# touch-24.net
KiCad netlist of a schematic drawn in Altium Designer
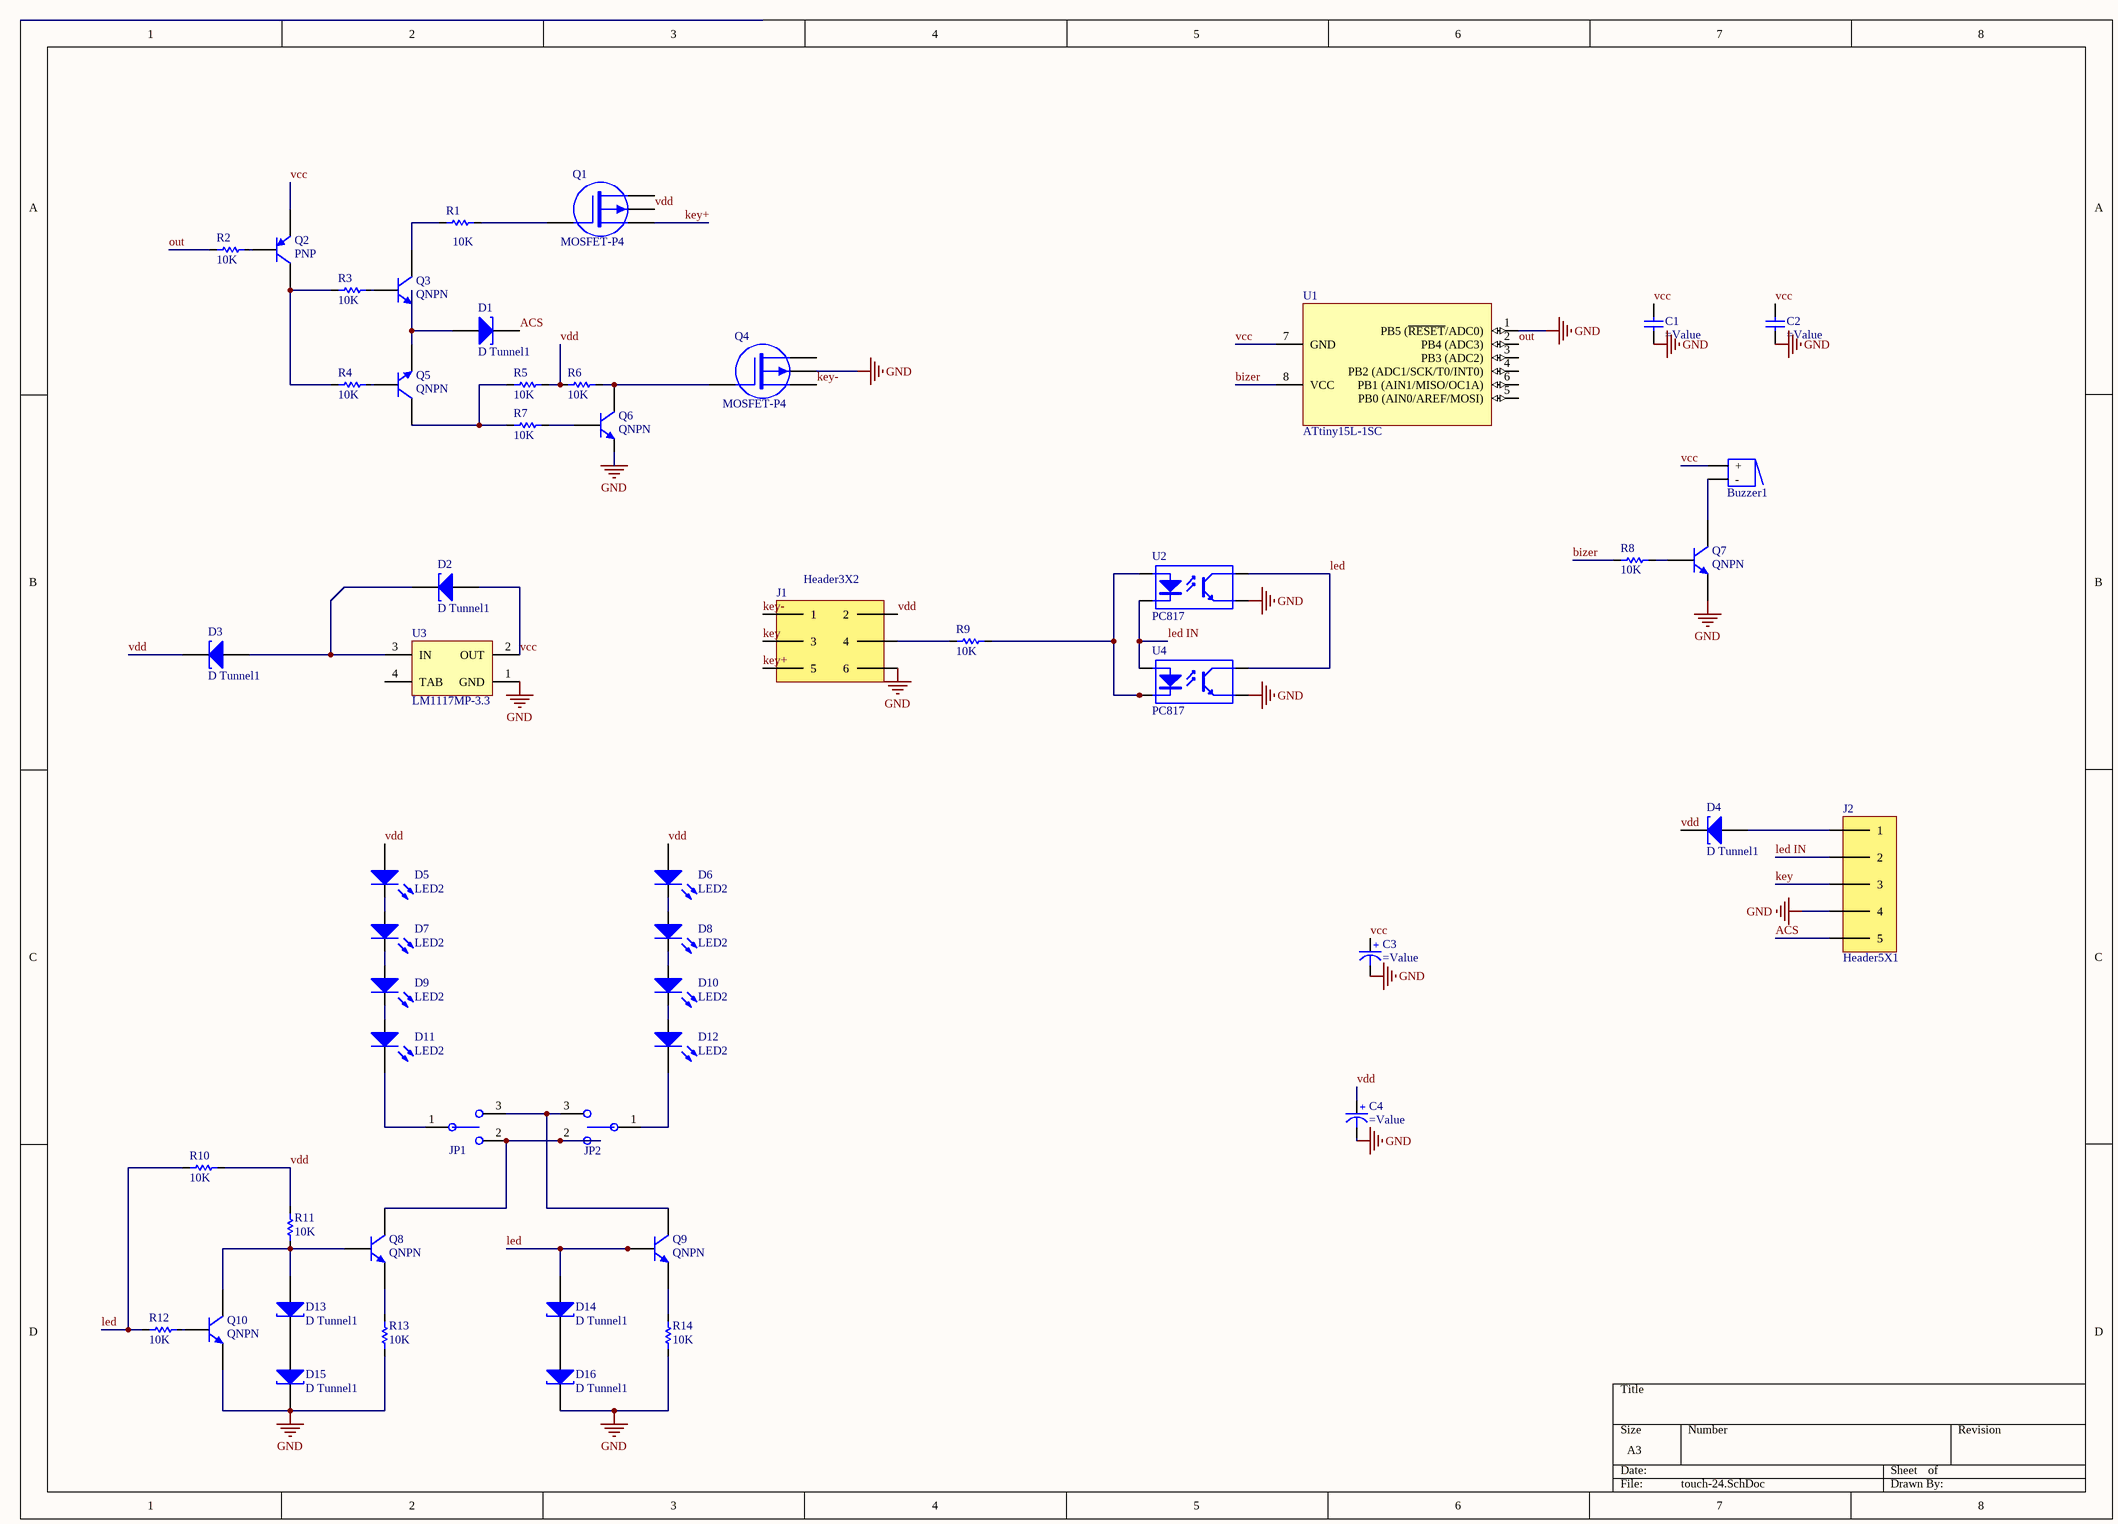
[diagram p0: touch-24.SchDoc]

(export (version "E")
  (design (tool "Eeschema 10.0.6"))
  (components
    (comp (ref "Buzzer1")
      (value "Buzzer")
      (footprint "BUZZER")
      (fields (field (name "DESIGNER") "Seyed Mohsen Ghasemain"))
      (libsource (lib "PicPars.com_usefully_Library") (part "Buzzer"))
    )
    (comp (ref "C1")
      (value "~")
      (footprint "CAP 1206")
      (description "Capacitor")
      (libsource (lib "AltiumLib1") (part "Capacitor"))
    )
    (comp (ref "C2")
      (value "~")
      (footprint "CAP 1206")
      (description "Capacitor")
      (libsource (lib "AltiumLib1") (part "Capacitor"))
    )
    (comp (ref "C3")
      (value "~")
      (footprint "ELEC-CAP-RAD10-20")
      (description "Electrolytic Capacitor")
      (libsource (lib "AltiumLib1") (part "Capacitor Electrolytic"))
    )
    (comp (ref "C4")
      (value "~")
      (footprint "ELEC-CAP-RAD15-30")
      (description "Electrolytic Capacitor")
      (libsource (lib "AltiumLib1") (part "Capacitor Electrolytic"))
    )
    (comp (ref "D1")
      (value "D Tunnel1")
      (footprint "3.2X1.6X1.1")
      (description "Tunnel Diode - RLC Model")
      (fields (field (name "PUBLISHER") "Altium Limited"))
      (libsource (lib "Miscellaneous Devices") (part "D Tunnel1"))
    )
    (comp (ref "D2")
      (value "D Tunnel1")
      (footprint "3.2X1.6X1.1")
      (description "Tunnel Diode - RLC Model")
      (fields (field (name "PUBLISHER") "Altium Limited"))
      (libsource (lib "Miscellaneous Devices") (part "D Tunnel1"))
    )
    (comp (ref "D3")
      (value "D Tunnel1")
      (footprint "3.2X1.6X1.1")
      (description "Tunnel Diode - RLC Model")
      (fields (field (name "PUBLISHER") "Altium Limited"))
      (libsource (lib "Miscellaneous Devices") (part "D Tunnel1"))
    )
    (comp (ref "D4")
      (value "D Tunnel1")
      (footprint "3.2X1.6X1.1")
      (description "Tunnel Diode - RLC Model")
      (fields (field (name "PUBLISHER") "Altium Limited"))
      (libsource (lib "Miscellaneous Devices") (part "D Tunnel1"))
    )
    (comp (ref "D5")
      (value "LED2")
      (footprint "3.2X1.6X1.1")
      (description "Typical RED, GREEN, YELLOW, AMBER GaAs LED")
      (fields (field (name "PUBLISHER") "Altium Limited"))
      (libsource (lib "Miscellaneous Devices") (part "LED2"))
    )
    (comp (ref "D6")
      (value "LED2")
      (footprint "3.2X1.6X1.1")
      (description "Typical RED, GREEN, YELLOW, AMBER GaAs LED")
      (fields (field (name "PUBLISHER") "Altium Limited"))
      (libsource (lib "Miscellaneous Devices") (part "LED2"))
    )
    (comp (ref "D7")
      (value "LED2")
      (footprint "3.2X1.6X1.1")
      (description "Typical RED, GREEN, YELLOW, AMBER GaAs LED")
      (fields (field (name "PUBLISHER") "Altium Limited"))
      (libsource (lib "Miscellaneous Devices") (part "LED2"))
    )
    (comp (ref "D8")
      (value "LED2")
      (footprint "3.2X1.6X1.1")
      (description "Typical RED, GREEN, YELLOW, AMBER GaAs LED")
      (fields (field (name "PUBLISHER") "Altium Limited"))
      (libsource (lib "Miscellaneous Devices") (part "LED2"))
    )
    (comp (ref "D9")
      (value "LED2")
      (footprint "3.2X1.6X1.1")
      (description "Typical RED, GREEN, YELLOW, AMBER GaAs LED")
      (fields (field (name "PUBLISHER") "Altium Limited"))
      (libsource (lib "Miscellaneous Devices") (part "LED2"))
    )
    (comp (ref "D10")
      (value "LED2")
      (footprint "3.2X1.6X1.1")
      (description "Typical RED, GREEN, YELLOW, AMBER GaAs LED")
      (fields (field (name "PUBLISHER") "Altium Limited"))
      (libsource (lib "Miscellaneous Devices") (part "LED2"))
    )
    (comp (ref "D11")
      (value "LED2")
      (footprint "3.2X1.6X1.1")
      (description "Typical RED, GREEN, YELLOW, AMBER GaAs LED")
      (fields (field (name "PUBLISHER") "Altium Limited"))
      (libsource (lib "Miscellaneous Devices") (part "LED2"))
    )
    (comp (ref "D12")
      (value "LED2")
      (footprint "3.2X1.6X1.1")
      (description "Typical RED, GREEN, YELLOW, AMBER GaAs LED")
      (fields (field (name "PUBLISHER") "Altium Limited"))
      (libsource (lib "Miscellaneous Devices") (part "LED2"))
    )
    (comp (ref "D13")
      (value "D Tunnel1")
      (footprint "3.2X1.6X1.1")
      (description "Tunnel Diode - RLC Model")
      (fields (field (name "PUBLISHER") "Altium Limited"))
      (libsource (lib "Miscellaneous Devices") (part "D Tunnel1"))
    )
    (comp (ref "D14")
      (value "D Tunnel1")
      (footprint "3.2X1.6X1.1")
      (description "Tunnel Diode - RLC Model")
      (fields (field (name "PUBLISHER") "Altium Limited"))
      (libsource (lib "Miscellaneous Devices") (part "D Tunnel1"))
    )
    (comp (ref "D15")
      (value "D Tunnel1")
      (footprint "3.2X1.6X1.1")
      (description "Tunnel Diode - RLC Model")
      (fields (field (name "PUBLISHER") "Altium Limited"))
      (libsource (lib "Miscellaneous Devices") (part "D Tunnel1"))
    )
    (comp (ref "D16")
      (value "D Tunnel1")
      (footprint "3.2X1.6X1.1")
      (description "Tunnel Diode - RLC Model")
      (fields (field (name "PUBLISHER") "Altium Limited"))
      (libsource (lib "Miscellaneous Devices") (part "D Tunnel1"))
    )
    (comp (ref "J1")
      (value "Header3X2")
      (footprint "HEADER 3X2")
      (libsource (lib "AltiumLib1") (part "Header3X2"))
    )
    (comp (ref "J2")
      (value "Header5X1")
      (footprint "HEADER 5X1")
      (libsource (lib "AltiumLib1") (part "Header5X1"))
    )
    (comp (ref "JP1")
      (value "Jumper Selector")
      (footprint "Jumper Selector")
      (libsource (lib "AltiumLib1") (part "Jumper Selector"))
    )
    (comp (ref "JP2")
      (value "Jumper Selector")
      (footprint "Jumper Selector")
      (libsource (lib "") (part "Jumper Selector_1"))
    )
    (comp (ref "Q1")
      (value "MOSFET-P4")
      (footprint "SOT223_N")
      (description "P-Channel MOSFET, Externally Terminated Substrate")
      (fields (field (name "PUBLISHER") "Altium Limited"))
      (libsource (lib "Miscellaneous Devices") (part "MOSFET-P4"))
    )
    (comp (ref "Q2")
      (value "PNP")
      (footprint "SOT-23B_N")
      (description "PNP Bipolar Transistor")
      (fields (field (name "PUBLISHER") "Altium Limited"))
      (libsource (lib "Miscellaneous Devices") (part "PNP"))
    )
    (comp (ref "Q3")
      (value "QNPN")
      (footprint "SOT-23B_L")
      (description "NPN Bipolar Transistor")
      (fields (field (name "PUBLISHER") "Altium Limited"))
      (libsource (lib "Miscellaneous Devices") (part "QNPN"))
    )
    (comp (ref "Q4")
      (value "MOSFET-P4")
      (footprint "SOT223_N")
      (description "P-Channel MOSFET, Externally Terminated Substrate")
      (fields (field (name "PUBLISHER") "Altium Limited"))
      (libsource (lib "Miscellaneous Devices") (part "MOSFET-P4"))
    )
    (comp (ref "Q5")
      (value "QNPN")
      (footprint "SOT-23B_L")
      (description "NPN Bipolar Transistor")
      (fields (field (name "PUBLISHER") "Altium Limited"))
      (libsource (lib "Miscellaneous Devices") (part "QNPN"))
    )
    (comp (ref "Q6")
      (value "QNPN")
      (footprint "SOT-23B_L")
      (description "NPN Bipolar Transistor")
      (fields (field (name "PUBLISHER") "Altium Limited"))
      (libsource (lib "Miscellaneous Devices") (part "QNPN"))
    )
    (comp (ref "Q7")
      (value "QNPN")
      (footprint "SOT-23B_L")
      (description "NPN Bipolar Transistor")
      (fields (field (name "PUBLISHER") "Altium Limited"))
      (libsource (lib "Miscellaneous Devices") (part "QNPN"))
    )
    (comp (ref "Q8")
      (value "QNPN")
      (footprint "SOT-23B_L")
      (description "NPN Bipolar Transistor")
      (fields (field (name "PUBLISHER") "Altium Limited"))
      (libsource (lib "Miscellaneous Devices") (part "QNPN"))
    )
    (comp (ref "Q9")
      (value "QNPN")
      (footprint "SOT-23B_L")
      (description "NPN Bipolar Transistor")
      (fields (field (name "PUBLISHER") "Altium Limited"))
      (libsource (lib "Miscellaneous Devices") (part "QNPN"))
    )
    (comp (ref "Q10")
      (value "QNPN")
      (footprint "SOT-23B_L")
      (description "NPN Bipolar Transistor")
      (fields (field (name "PUBLISHER") "Altium Limited"))
      (libsource (lib "Miscellaneous Devices") (part "QNPN"))
    )
    (comp (ref "R1")
      (value "10K")
      (footprint "RES 1206 (3216X08L)")
      (description "Resistor")
      (fields (field (name "TOLERANCE") "5%") (field (name "POWER") "1/4 W"))
      (libsource (lib "AltiumLib1") (part "Resistor"))
    )
    (comp (ref "R2")
      (value "10K")
      (footprint "RES 1206 (3216X08L)")
      (description "Resistor")
      (fields (field (name "TOLERANCE") "5%") (field (name "POWER") "1/4 W"))
      (libsource (lib "AltiumLib1") (part "Resistor"))
    )
    (comp (ref "R3")
      (value "10K")
      (footprint "RES 1206 (3216X08L)")
      (description "Resistor")
      (fields (field (name "TOLERANCE") "5%") (field (name "POWER") "1/4 W"))
      (libsource (lib "AltiumLib1") (part "Resistor"))
    )
    (comp (ref "R4")
      (value "10K")
      (footprint "RES 1206 (3216X08L)")
      (description "Resistor")
      (fields (field (name "TOLERANCE") "5%") (field (name "POWER") "1/4 W"))
      (libsource (lib "AltiumLib1") (part "Resistor"))
    )
    (comp (ref "R5")
      (value "10K")
      (footprint "RES 1206 (3216X08L)")
      (description "Resistor")
      (fields (field (name "TOLERANCE") "5%") (field (name "POWER") "1/4 W"))
      (libsource (lib "AltiumLib1") (part "Resistor"))
    )
    (comp (ref "R6")
      (value "10K")
      (footprint "RES 1206 (3216X08L)")
      (description "Resistor")
      (fields (field (name "TOLERANCE") "5%") (field (name "POWER") "1/4 W"))
      (libsource (lib "AltiumLib1") (part "Resistor"))
    )
    (comp (ref "R7")
      (value "10K")
      (footprint "RES 1206 (3216X08L)")
      (description "Resistor")
      (fields (field (name "TOLERANCE") "5%") (field (name "POWER") "1/4 W"))
      (libsource (lib "AltiumLib1") (part "Resistor"))
    )
    (comp (ref "R8")
      (value "10K")
      (footprint "RES 1206 (3216X08L)")
      (description "Resistor")
      (fields (field (name "TOLERANCE") "5%") (field (name "POWER") "1/4 W"))
      (libsource (lib "AltiumLib1") (part "Resistor"))
    )
    (comp (ref "R9")
      (value "10K")
      (footprint "RES 1206 (3216X08L)")
      (description "Resistor")
      (fields (field (name "TOLERANCE") "5%") (field (name "POWER") "1/4 W"))
      (libsource (lib "AltiumLib1") (part "Resistor"))
    )
    (comp (ref "R10")
      (value "10K")
      (footprint "RES 1206 (3216X08L)")
      (description "Resistor")
      (fields (field (name "TOLERANCE") "5%") (field (name "POWER") "1/4 W"))
      (libsource (lib "AltiumLib1") (part "Resistor"))
    )
    (comp (ref "R11")
      (value "10K")
      (footprint "RES 1206 (3216X08L)")
      (description "Resistor")
      (fields (field (name "TOLERANCE") "5%") (field (name "POWER") "1/4 W"))
      (libsource (lib "AltiumLib1") (part "Resistor"))
    )
    (comp (ref "R12")
      (value "10K")
      (footprint "RES 1206 (3216X08L)")
      (description "Resistor")
      (fields (field (name "TOLERANCE") "5%") (field (name "POWER") "1/4 W"))
      (libsource (lib "AltiumLib1") (part "Resistor"))
    )
    (comp (ref "R13")
      (value "10K")
      (footprint "RES 1206 (3216X08L)")
      (description "Resistor")
      (fields (field (name "TOLERANCE") "5%") (field (name "POWER") "1/4 W"))
      (libsource (lib "AltiumLib1") (part "Resistor"))
    )
    (comp (ref "R14")
      (value "10K")
      (footprint "RES 1206 (3216X08L)")
      (description "Resistor")
      (fields (field (name "TOLERANCE") "5%") (field (name "POWER") "1/4 W"))
      (libsource (lib "AltiumLib1") (part "Resistor"))
    )
    (comp (ref "U1")
      (value "ATtiny15L-1SC")
      (footprint "8S2_N")
      (description "8-Bit AVR Microcontroller with 1K Byte of Flash Memory")
      (fields (field (name "PUBLISHER") "Altium Limited"))
      (libsource (lib "Atmel Microcontroller 8-Bit AVR") (part "ATtiny15L-1SC"))
    )
    (comp (ref "U2")
      (value "PC817")
      (footprint "DIP4")
      (description "4-Pin Phototransistor Optocoupler")
      (libsource (lib "AltiumLib1") (part "OPTCOUPLER_01"))
    )
    (comp (ref "U3")
      (value "LM1117MP-3.3")
      (footprint "Miscellaneous Devices:SOT89L")
      (description "800mA Low-Dropout Linear Regulator")
      (fields
        (field (name "MANUFACTURER") "National Semiconductor")
        (field (name "DIGIKEYPARTNUMBER") "LM1117MP-3.3CT-ND")
        (field (name "PUBLISHER") "Altium Limited")
      )
      (libsource (lib "NSC LDO") (part "LM1117MP-3.3"))
    )
    (comp (ref "U4")
      (value "PC817")
      (footprint "DIP4")
      (description "4-Pin Phototransistor Optocoupler")
      (libsource (lib "AltiumLib1") (part "OPTCOUPLER_01"))
    )
  )
  (nets
    (net (code "1") (name "/ACS") (class "Default")
      (node (ref "D1") (pin "2") (pinfunction "K_2") (pintype "passive"))
      (node (ref "J2") (pin "5") (pinfunction "5_5") (pintype "passive"))
    )
    (net (code "2") (name "/bizer") (class "Default")
      (node (ref "R8") (pin "1") (pinfunction "1_1") (pintype "passive"))
      (node (ref "U1") (pin "8") (pinfunction "VCC_8") (pintype "power_in"))
    )
    (net (code "3") (name "/key") (class "Default")
      (node (ref "J1") (pin "3") (pinfunction "3_3") (pintype "passive"))
      (node (ref "J2") (pin "3") (pinfunction "3_3") (pintype "passive"))
    )
    (net (code "4") (name "/key+") (class "Default")
      (node (ref "J1") (pin "5") (pinfunction "5_5") (pintype "passive"))
      (node (ref "Q1") (pin "4") (pinfunction "S_4") (pintype "passive"))
    )
    (net (code "5") (name "/key-") (class "Default")
      (node (ref "J1") (pin "1") (pinfunction "1_1") (pintype "passive"))
      (node (ref "Q4") (pin "4") (pinfunction "S_4") (pintype "passive"))
    )
    (net (code "6") (name "/led") (class "Default")
      (node (ref "D14") (pin "1") (pinfunction "A_1") (pintype "passive"))
      (node (ref "Q9") (pin "2") (pinfunction "B_2") (pintype "passive"))
      (node (ref "R10") (pin "1") (pinfunction "1_1") (pintype "passive"))
      (node (ref "R12") (pin "1") (pinfunction "1_1") (pintype "passive"))
      (node (ref "U2") (pin "4") (pinfunction "C_4") (pintype "passive"))
      (node (ref "U4") (pin "4") (pinfunction "C_4") (pintype "passive"))
    )
    (net (code "7") (name "/led IN") (class "Default")
      (node (ref "J2") (pin "2") (pinfunction "2_2") (pintype "passive"))
      (node (ref "U2") (pin "2") (pinfunction "K_2") (pintype "passive"))
      (node (ref "U4") (pin "1") (pinfunction "A_1") (pintype "passive"))
    )
    (net (code "8") (name "/out") (class "Default")
      (node (ref "R2") (pin "1") (pinfunction "1_1") (pintype "passive"))
      (node (ref "U1") (pin "2") (pinfunction "PB4_(ADC3)_2") (pintype "bidirectional"))
    )
    (net (code "9") (name "/vcc") (class "Default")
      (node (ref "Buzzer1") (pin "1") (pinfunction "+_1") (pintype "passive"))
      (node (ref "C1") (pin "2") (pinfunction "-_2") (pintype "passive"))
      (node (ref "C2") (pin "2") (pinfunction "-_2") (pintype "passive"))
      (node (ref "C3") (pin "2") (pinfunction "+_2") (pintype "passive"))
      (node (ref "D2") (pin "1") (pinfunction "A_1") (pintype "passive"))
      (node (ref "Q2") (pin "3") (pinfunction "E_3") (pintype "passive"))
      (node (ref "U1") (pin "7") (pinfunction "GND_7") (pintype "power_in"))
      (node (ref "U3") (pin "2") (pinfunction "OUT_2") (pintype "power_in"))
    )
    (net (code "10") (name "/vdd") (class "Default")
      (node (ref "C4") (pin "2") (pinfunction "+_2") (pintype "passive"))
      (node (ref "D3") (pin "2") (pinfunction "K_2") (pintype "passive"))
      (node (ref "D4") (pin "2") (pinfunction "K_2") (pintype "passive"))
      (node (ref "D5") (pin "1") (pinfunction "A_1") (pintype "passive"))
      (node (ref "D6") (pin "1") (pinfunction "A_1") (pintype "passive"))
      (node (ref "J1") (pin "2") (pinfunction "2_2") (pintype "passive"))
      (node (ref "Q1") (pin "3") (pinfunction "U_3") (pintype "passive"))
      (node (ref "R10") (pin "2") (pinfunction "2_2") (pintype "passive"))
      (node (ref "R11") (pin "2") (pinfunction "2_2") (pintype "passive"))
      (node (ref "R5") (pin "2") (pinfunction "2_2") (pintype "passive"))
      (node (ref "R6") (pin "1") (pinfunction "1_1") (pintype "passive"))
    )
    (net (code "11") (name "GND") (class "Default")
      (node (ref "C1") (pin "1") (pinfunction "+_1") (pintype "passive"))
      (node (ref "C2") (pin "1") (pinfunction "+_1") (pintype "passive"))
      (node (ref "C3") (pin "1") (pinfunction "-_1") (pintype "passive"))
      (node (ref "C4") (pin "1") (pinfunction "-_1") (pintype "passive"))
      (node (ref "D15") (pin "2") (pinfunction "K_2") (pintype "passive"))
      (node (ref "D16") (pin "2") (pinfunction "K_2") (pintype "passive"))
      (node (ref "J1") (pin "6") (pinfunction "6_6") (pintype "passive"))
      (node (ref "J2") (pin "4") (pinfunction "4_4") (pintype "passive"))
      (node (ref "Q10") (pin "3") (pinfunction "E_3") (pintype "passive"))
      (node (ref "Q4") (pin "3") (pinfunction "U_3") (pintype "passive"))
      (node (ref "Q6") (pin "3") (pinfunction "E_3") (pintype "passive"))
      (node (ref "Q7") (pin "3") (pinfunction "E_3") (pintype "passive"))
      (node (ref "R13") (pin "1") (pinfunction "1_1") (pintype "passive"))
      (node (ref "R14") (pin "1") (pinfunction "1_1") (pintype "passive"))
      (node (ref "U1") (pin "1") (pinfunction "PB5_(~{RESET}/ADC0)_1") (pintype "bidirectional"))
      (node (ref "U2") (pin "3") (pinfunction "E_3") (pintype "passive"))
      (node (ref "U3") (pin "1") (pinfunction "GND_1") (pintype "power_in"))
      (node (ref "U4") (pin "3") (pinfunction "E_3") (pintype "passive"))
    )
    (net (code "12") (name "Net-(Buzzer1--)") (class "Default")
      (node (ref "Buzzer1") (pin "2") (pinfunction "-_2") (pintype "passive"))
      (node (ref "Q7") (pin "1") (pinfunction "C_1") (pintype "passive"))
    )
    (net (code "13") (name "Net-(D1-A)") (class "Default")
      (node (ref "D1") (pin "1") (pinfunction "A_1") (pintype "passive"))
      (node (ref "Q3") (pin "3") (pinfunction "E_3") (pintype "passive"))
      (node (ref "Q5") (pin "3") (pinfunction "E_3") (pintype "passive"))
    )
    (net (code "14") (name "Net-(D2-K)") (class "Default")
      (node (ref "D2") (pin "2") (pinfunction "K_2") (pintype "passive"))
      (node (ref "D3") (pin "1") (pinfunction "A_1") (pintype "passive"))
      (node (ref "U3") (pin "3") (pinfunction "IN_3") (pintype "power_in"))
    )
    (net (code "15") (name "Net-(D4-A)") (class "Default")
      (node (ref "D4") (pin "1") (pinfunction "A_1") (pintype "passive"))
      (node (ref "J2") (pin "1") (pinfunction "1_1") (pintype "passive"))
    )
    (net (code "16") (name "Net-(D5-K)") (class "Default")
      (node (ref "D5") (pin "2") (pinfunction "K_2") (pintype "passive"))
      (node (ref "D7") (pin "1") (pinfunction "A_1") (pintype "passive"))
    )
    (net (code "17") (name "Net-(D6-K)") (class "Default")
      (node (ref "D6") (pin "2") (pinfunction "K_2") (pintype "passive"))
      (node (ref "D8") (pin "1") (pinfunction "A_1") (pintype "passive"))
    )
    (net (code "18") (name "Net-(D7-K)") (class "Default")
      (node (ref "D7") (pin "2") (pinfunction "K_2") (pintype "passive"))
      (node (ref "D9") (pin "1") (pinfunction "A_1") (pintype "passive"))
    )
    (net (code "19") (name "Net-(D10-A)") (class "Default")
      (node (ref "D10") (pin "1") (pinfunction "A_1") (pintype "passive"))
      (node (ref "D8") (pin "2") (pinfunction "K_2") (pintype "passive"))
    )
    (net (code "20") (name "Net-(D10-K)") (class "Default")
      (node (ref "D10") (pin "2") (pinfunction "K_2") (pintype "passive"))
      (node (ref "D12") (pin "1") (pinfunction "A_1") (pintype "passive"))
    )
    (net (code "21") (name "Net-(D11-A)") (class "Default")
      (node (ref "D11") (pin "1") (pinfunction "A_1") (pintype "passive"))
      (node (ref "D9") (pin "2") (pinfunction "K_2") (pintype "passive"))
    )
    (net (code "22") (name "Net-(D11-K)") (class "Default")
      (node (ref "D11") (pin "2") (pinfunction "K_2") (pintype "passive"))
      (node (ref "JP1") (pin "1") (pinfunction "1_1") (pintype "passive"))
    )
    (net (code "23") (name "Net-(D12-K)") (class "Default")
      (node (ref "D12") (pin "2") (pinfunction "K_2") (pintype "passive"))
      (node (ref "JP2") (pin "1") (pinfunction "1_1") (pintype "passive"))
    )
    (net (code "24") (name "Net-(D13-A)") (class "Default")
      (node (ref "D13") (pin "1") (pinfunction "A_1") (pintype "passive"))
      (node (ref "Q10") (pin "1") (pinfunction "C_1") (pintype "passive"))
      (node (ref "Q8") (pin "2") (pinfunction "B_2") (pintype "passive"))
      (node (ref "R11") (pin "1") (pinfunction "1_1") (pintype "passive"))
    )
    (net (code "25") (name "Net-(D13-K)") (class "Default")
      (node (ref "D13") (pin "2") (pinfunction "K_2") (pintype "passive"))
      (node (ref "D15") (pin "1") (pinfunction "A_1") (pintype "passive"))
    )
    (net (code "26") (name "Net-(D14-K)") (class "Default")
      (node (ref "D14") (pin "2") (pinfunction "K_2") (pintype "passive"))
      (node (ref "D16") (pin "1") (pinfunction "A_1") (pintype "passive"))
    )
    (net (code "27") (name "Net-(J1-Pad4)") (class "Default")
      (node (ref "J1") (pin "4") (pinfunction "4_4") (pintype "passive"))
      (node (ref "R9") (pin "1") (pinfunction "1_1") (pintype "passive"))
    )
    (net (code "28") (name "Net-(Q1-G)") (class "Default")
      (node (ref "Q1") (pin "1") (pinfunction "G_1") (pintype "passive"))
      (node (ref "R1") (pin "2") (pinfunction "2_2") (pintype "passive"))
    )
    (net (code "29") (name "Net-(Q2-B)") (class "Default")
      (node (ref "Q2") (pin "2") (pinfunction "B_2") (pintype "passive"))
      (node (ref "R2") (pin "2") (pinfunction "2_2") (pintype "passive"))
    )
    (net (code "30") (name "Net-(Q2-C)") (class "Default")
      (node (ref "Q2") (pin "1") (pinfunction "C_1") (pintype "passive"))
      (node (ref "R3") (pin "1") (pinfunction "1_1") (pintype "passive"))
      (node (ref "R4") (pin "1") (pinfunction "1_1") (pintype "passive"))
    )
    (net (code "31") (name "Net-(Q3-B)") (class "Default")
      (node (ref "Q3") (pin "2") (pinfunction "B_2") (pintype "passive"))
      (node (ref "R3") (pin "2") (pinfunction "2_2") (pintype "passive"))
    )
    (net (code "32") (name "Net-(Q3-C)") (class "Default")
      (node (ref "Q3") (pin "1") (pinfunction "C_1") (pintype "passive"))
      (node (ref "R1") (pin "1") (pinfunction "1_1") (pintype "passive"))
    )
    (net (code "33") (name "Net-(Q4-G)") (class "Default")
      (node (ref "Q4") (pin "1") (pinfunction "G_1") (pintype "passive"))
      (node (ref "Q6") (pin "1") (pinfunction "C_1") (pintype "passive"))
      (node (ref "R6") (pin "2") (pinfunction "2_2") (pintype "passive"))
    )
    (net (code "34") (name "Net-(Q5-B)") (class "Default")
      (node (ref "Q5") (pin "2") (pinfunction "B_2") (pintype "passive"))
      (node (ref "R4") (pin "2") (pinfunction "2_2") (pintype "passive"))
    )
    (net (code "35") (name "Net-(Q5-C)") (class "Default")
      (node (ref "Q5") (pin "1") (pinfunction "C_1") (pintype "passive"))
      (node (ref "R5") (pin "1") (pinfunction "1_1") (pintype "passive"))
      (node (ref "R7") (pin "1") (pinfunction "1_1") (pintype "passive"))
    )
    (net (code "36") (name "Net-(Q6-B)") (class "Default")
      (node (ref "Q6") (pin "2") (pinfunction "B_2") (pintype "passive"))
      (node (ref "R7") (pin "2") (pinfunction "2_2") (pintype "passive"))
    )
    (net (code "37") (name "Net-(Q7-B)") (class "Default")
      (node (ref "Q7") (pin "2") (pinfunction "B_2") (pintype "passive"))
      (node (ref "R8") (pin "2") (pinfunction "2_2") (pintype "passive"))
    )
    (net (code "38") (name "Net-(Q8-C)") (class "Default")
      (node (ref "JP1") (pin "2") (pinfunction "2_2") (pintype "passive"))
      (node (ref "JP2") (pin "2") (pinfunction "2_2") (pintype "passive"))
      (node (ref "Q8") (pin "1") (pinfunction "C_1") (pintype "passive"))
    )
    (net (code "39") (name "Net-(Q8-E)") (class "Default")
      (node (ref "Q8") (pin "3") (pinfunction "E_3") (pintype "passive"))
      (node (ref "R13") (pin "2") (pinfunction "2_2") (pintype "passive"))
    )
    (net (code "40") (name "Net-(Q9-C)") (class "Default")
      (node (ref "JP1") (pin "3") (pinfunction "3_3") (pintype "passive"))
      (node (ref "JP2") (pin "3") (pinfunction "3_3") (pintype "passive"))
      (node (ref "Q9") (pin "1") (pinfunction "C_1") (pintype "passive"))
    )
    (net (code "41") (name "Net-(Q9-E)") (class "Default")
      (node (ref "Q9") (pin "3") (pinfunction "E_3") (pintype "passive"))
      (node (ref "R14") (pin "2") (pinfunction "2_2") (pintype "passive"))
    )
    (net (code "42") (name "Net-(Q10-B)") (class "Default")
      (node (ref "Q10") (pin "2") (pinfunction "B_2") (pintype "passive"))
      (node (ref "R12") (pin "2") (pinfunction "2_2") (pintype "passive"))
    )
    (net (code "43") (name "Net-(U2-A)") (class "Default")
      (node (ref "R9") (pin "2") (pinfunction "2_2") (pintype "passive"))
      (node (ref "U2") (pin "1") (pinfunction "A_1") (pintype "passive"))
      (node (ref "U4") (pin "2") (pinfunction "K_2") (pintype "passive"))
    )
    (net (code "44") (name "unconnected-(Q1-D-Pad2)") (class "Default")
      (node (ref "Q1") (pin "2") (pinfunction "D_2") (pintype "passive"))
    )
    (net (code "45") (name "unconnected-(Q4-D-Pad2)") (class "Default")
      (node (ref "Q4") (pin "2") (pinfunction "D_2") (pintype "passive"))
    )
    (net (code "46") (name "unconnected-(U1-PB0_(AIN0{slash}AREF{slash}MOSI)-Pad5)") (class "Default")
      (node (ref "U1") (pin "5") (pinfunction "PB0_(AIN0/AREF/MOSI)_5") (pintype "bidirectional"))
    )
    (net (code "47") (name "unconnected-(U1-PB1_(AIN1{slash}MISO{slash}OC1A)-Pad6)") (class "Default")
      (node (ref "U1") (pin "6") (pinfunction "PB1_(AIN1/MISO/OC1A)_6") (pintype "bidirectional"))
    )
    (net (code "48") (name "unconnected-(U1-PB2_(ADC1{slash}SCK{slash}T0{slash}INT0)-Pad4)") (class "Default")
      (node (ref "U1") (pin "4") (pinfunction "PB2_(ADC1/SCK/T0/INT0)_4") (pintype "bidirectional"))
    )
    (net (code "49") (name "unconnected-(U1-PB3_(ADC2)-Pad3)") (class "Default")
      (node (ref "U1") (pin "3") (pinfunction "PB3_(ADC2)_3") (pintype "bidirectional"))
    )
    (net (code "50") (name "unconnected-(U3-TAB-Pad4)") (class "Default")
      (node (ref "U3") (pin "4") (pinfunction "TAB_4") (pintype "power_in"))
    )
  )
)
